# CIRCUIT.net
KiCad netlist of a schematic drawn in Altium Designer
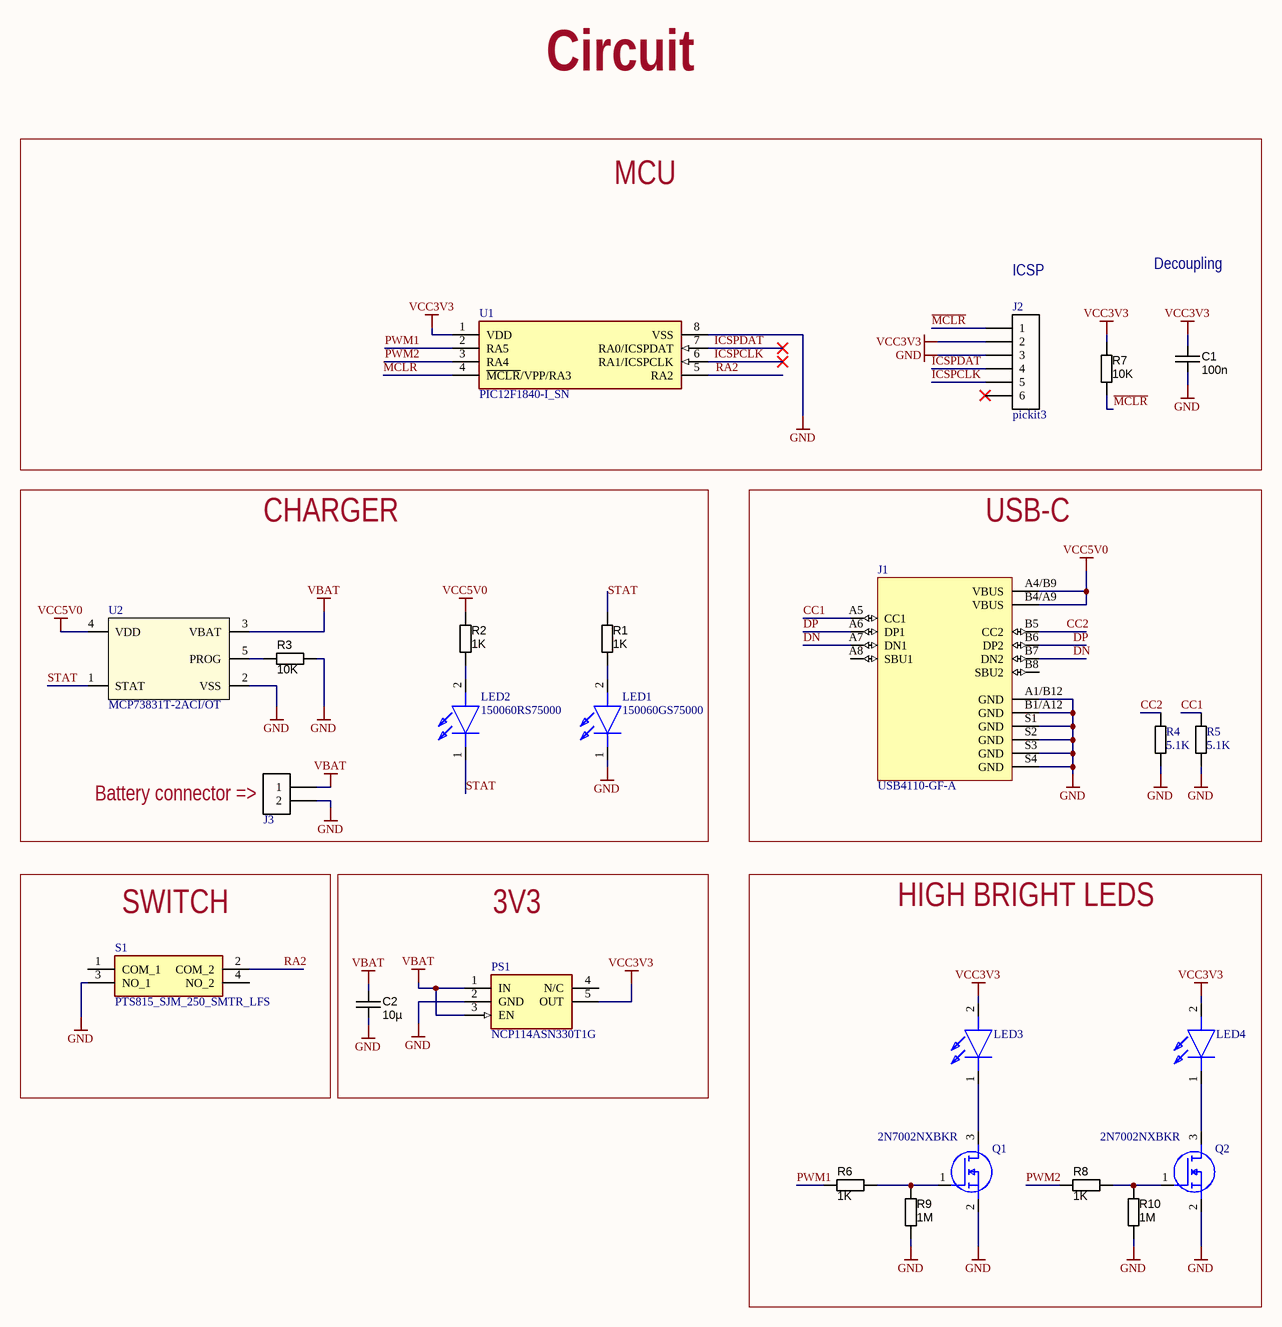
[diagram p0: CIRCUIT.SchDoc]

(export (version "E")
  (design (tool "Eeschema 10.0.6"))
  (components
    (comp (ref "C1")
      (value "100n")
      (footprint "CAPC1608X90N")
      (description "Capacitor SMD Cer 100nF 10% 50V X7R 0603")
      (fields (field (name "TOLERANCE") "±10%") (field (name "Comment") "approved sub OK"))
      (libsource (lib "PBL - Capacitors") (part "CAPC_100n_0603_X7R_50V_10%"))
    )
    (comp (ref "C2")
      (value "10µ")
      (footprint "CAPC3216X180N")
      (description "Capacitor SMD Cer 10uF 10% 25V X7R 1206")
      (fields (field (name "TOLERANCE") "±10%") (field (name "Comment") "approved sub OK"))
      (libsource (lib "jpnbino") (part "CAPC_10u_1206_25V"))
    )
    (comp (ref "J1")
      (value "USB4110-GF-A")
      (footprint "chico:GCT_USB4110-GF-A")
      (fields (field (name "MF") "GCT") (field (name "DIGI-KEY_PART_NUMBER") "2073-USB4110-GF-A-1-ND"))
      (libsource (lib "chico") (part "USB4110-GF-A"))
    )
    (comp (ref "J2")
      (value "pickit3")
      (footprint "CONN_ICSP")
      (description "CONN PROG PICKIT3 6VIAS")
      (libsource (lib "jpnbino") (part "CONN PROG PICKIT3"))
    )
    (comp (ref "J3")
      (value "S2B-PH-K-S(LF)(SN)")
      (footprint "JST-S2B-PH-K-S_V")
      (fields (field (name "TOLERANCE") "20%"))
      (libsource (lib "jpnbino") (part "CONN JST 2P 2MM"))
    )
    (comp (ref "LED1")
      (value "150060GS75000")
      (footprint "SamacSys:LEDC1608X80N")
      (description "LED")
      (fields (field (name "MOUSER PART NUMBER") "710-150060GS75000"))
      (libsource (lib "*") (part "150060GS75000"))
    )
    (comp (ref "LED2")
      (value "150060RS75000")
      (footprint "SamacSys:LEDC1608X80N")
      (description "LED")
      (fields (field (name "MOUSER PART NUMBER") "710-150060RS75000"))
      (libsource (lib "*") (part "150060RS75000"))
    )
    (comp (ref "LED3")
      (value "S1W0-2835408003-0000003S-00005")
      (footprint "SamacSys:STW8A12DMinJ18CAAll")
      (description "LED")
      (libsource (lib "SamacSys") (part "S1W0-2835408003-0000003S-00005"))
    )
    (comp (ref "LED4")
      (value "S1W0-2835408003-0000003S-00005")
      (footprint "SamacSys:STW8A12DMinJ18CAAll")
      (description "LED")
      (libsource (lib "SamacSys") (part "S1W0-2835408003-0000003S-00005"))
    )
    (comp (ref "PS1")
      (value "NCP114ASN330T1G")
      (footprint "SamacSys:SOT95P275X110-5N")
      (description "Power Supply")
      (fields (field (name "MOUSER PART NUMBER") "863-NCP114ASN330T1G"))
      (libsource (lib "*") (part "NCP114ASN330T1G"))
    )
    (comp (ref "Q1")
      (value "2N7002NXBKR")
      (footprint "SamacSys:SOT95P230X110-3N")
      (description "MOSFET (N-Channel)")
      (fields (field (name "MOUSER PART NUMBER") "771-2N7002NXBKR"))
      (libsource (lib "*") (part "2N7002NXBKR"))
    )
    (comp (ref "Q2")
      (value "2N7002NXBKR")
      (footprint "SamacSys:SOT95P230X110-3N")
      (description "MOSFET (N-Channel)")
      (fields (field (name "MOUSER PART NUMBER") "771-2N7002NXBKR"))
      (libsource (lib "*") (part "2N7002NXBKR"))
    )
    (comp (ref "R1")
      (value "1K")
      (footprint "RESC1608X55N")
      (description "Resistor SMD chip 1k Ohm 0.1W 5% 0603")
      (fields (field (name "TOLERANCE") "±5%") (field (name "Comment") "Thick Film"))
      (libsource (lib "PBL - Resistors") (part "RES_1K_0603_5%"))
    )
    (comp (ref "R2")
      (value "1K")
      (footprint "RESC1608X55N")
      (description "Resistor SMD chip 1k Ohm 0.1W 5% 0603")
      (fields (field (name "TOLERANCE") "±5%") (field (name "Comment") "Thick Film"))
      (libsource (lib "PBL - Resistors") (part "RES_1K_0603_5%"))
    )
    (comp (ref "R3")
      (value "10K")
      (footprint "RESC1608X55N")
      (description "Resistor SMD chip 10k Ohm 0.1W 5% 0603")
      (fields (field (name "TOLERANCE") "±5%") (field (name "Comment") "Thick Film"))
      (libsource (lib "") (part "RES_10K_0603_5%_1"))
    )
    (comp (ref "R4")
      (value "5.1K")
      (footprint "RESC1608X55N")
      (fields (field (name "Comment") "RES 5.1K OHM 5% 1/10W 0603"))
      (libsource (lib "jpnbino") (part "RES 5.1K OHM 5% 1/10W 0603"))
    )
    (comp (ref "R5")
      (value "5.1K")
      (footprint "RESC1608X55N")
      (fields (field (name "Comment") "RES 5.1K OHM 5% 1/10W 0603"))
      (libsource (lib "jpnbino") (part "RES 5.1K OHM 5% 1/10W 0603"))
    )
    (comp (ref "R6")
      (value "1K")
      (footprint "RESC1608X55N")
      (description "Resistor SMD chip 1k Ohm 0.1W 5% 0603")
      (fields (field (name "TOLERANCE") "±5%") (field (name "Comment") "Thick Film"))
      (libsource (lib "RRutledge") (part "RES_1K_0603_5%"))
    )
    (comp (ref "R7")
      (value "10K")
      (footprint "RESC1608X55N")
      (description "Resistor SMD chip 10k Ohm 0.1W 5% 0603")
      (fields (field (name "TOLERANCE") "±5%") (field (name "Comment") "Thick Film"))
      (libsource (lib "PBL - Resistors") (part "RES_10K_0603_5%"))
    )
    (comp (ref "R8")
      (value "1K")
      (footprint "RESC1608X55N")
      (description "Resistor SMD chip 1k Ohm 0.1W 5% 0603")
      (fields (field (name "TOLERANCE") "±5%") (field (name "Comment") "Thick Film"))
      (libsource (lib "RRutledge") (part "RES_1K_0603_5%"))
    )
    (comp (ref "R9")
      (value "1M")
      (footprint "RESC1608X55N")
      (description "Resistor SMD chip 1M Ohm 0.1W 5% 0603")
      (fields (field (name "TOLERANCE") "±5%") (field (name "Comment") "Thick Film"))
      (libsource (lib "RRutledge") (part "RES_1M_0603_5%"))
    )
    (comp (ref "R10")
      (value "1M")
      (footprint "RESC1608X55N")
      (description "Resistor SMD chip 1M Ohm 0.1W 5% 0603")
      (fields (field (name "TOLERANCE") "±5%") (field (name "Comment") "Thick Film"))
      (libsource (lib "RRutledge") (part "RES_1M_0603_5%"))
    )
    (comp (ref "S1")
      (value "PTS815_SJM_250_SMTR_LFS")
      (footprint "SamacSys:PTS815SJM250SMTRLFS")
      (description "Switch")
      (fields
        (field (name "MANUFACTURER_PART_NUMBER") "PTS815 SJM 250 SMTR LFS")
        (field (name "MOUSER PART NUMBER") "611-PTS815SJM250SMTR")
      )
      (libsource (lib "*") (part "PTS815_SJM_250_SMTR_LFS"))
    )
    (comp (ref "U1")
      (value "PIC12F1840-I_SN")
      (footprint "SamacSys:SOIC127P600X175-8N")
      (description "Integrated Circuit")
      (fields
        (field (name "MANUFACTURER_PART_NUMBER") "PIC12F1840-I/SN")
        (field (name "MOUSER PART NUMBER") "579-PIC12F1840-I/SN")
      )
      (libsource (lib "*") (part "PIC12F1840-I_SN"))
    )
    (comp (ref "U2")
      (value "MCP73831T-2ACI/OT")
      (footprint "chico:SOT-23-5_MC_MCH")
      (description "No Description Available")
      (fields (field (name "COPYRIGHT") "Copyright (C) 2018 Accelerated Designs. All rights reserved"))
      (libsource (lib "chico") (part "MCP73831T-2ACI/O"))
    )
  )
  (nets
    (net (code "1") (name "/CC1") (class "Default")
      (node (ref "J1") (pin "A5") (pinfunction "CC1_A5") (pintype "bidirectional"))
      (node (ref "R5") (pin "2") (pinfunction "2_2") (pintype "passive"))
    )
    (net (code "2") (name "/CC2") (class "Default")
      (node (ref "J1") (pin "B5") (pinfunction "CC2_B5") (pintype "bidirectional"))
      (node (ref "R4") (pin "2") (pinfunction "2_2") (pintype "passive"))
    )
    (net (code "3") (name "/DN") (class "Default")
      (node (ref "J1") (pin "A7") (pinfunction "DN1_A7") (pintype "bidirectional"))
      (node (ref "J1") (pin "B7") (pinfunction "DN2_B7") (pintype "bidirectional"))
    )
    (net (code "4") (name "/DP") (class "Default")
      (node (ref "J1") (pin "A6") (pinfunction "DP1_A6") (pintype "bidirectional"))
      (node (ref "J1") (pin "B6") (pinfunction "DP2_B6") (pintype "bidirectional"))
    )
    (net (code "5") (name "/ICSPCLK") (class "Default")
      (node (ref "J2") (pin "5") (pinfunction "5_5") (pintype "passive"))
      (node (ref "U1") (pin "6") (pinfunction "RA1/ICSPCLK_6") (pintype "input"))
    )
    (net (code "6") (name "/ICSPDAT") (class "Default")
      (node (ref "J2") (pin "4") (pinfunction "4_4") (pintype "passive"))
      (node (ref "U1") (pin "7") (pinfunction "RA0/ICSPDAT_7") (pintype "input"))
    )
    (net (code "7") (name "/PWM1") (class "Default")
      (node (ref "R6") (pin "1") (pinfunction "1_1") (pintype "passive"))
      (node (ref "U1") (pin "2") (pinfunction "RA5_2") (pintype "passive"))
    )
    (net (code "8") (name "/PWM2") (class "Default")
      (node (ref "R8") (pin "1") (pinfunction "1_1") (pintype "passive"))
      (node (ref "U1") (pin "3") (pinfunction "RA4_3") (pintype "passive"))
    )
    (net (code "9") (name "/RA2") (class "Default")
      (node (ref "S1") (pin "2") (pinfunction "COM_2_2") (pintype "passive"))
      (node (ref "U1") (pin "5") (pinfunction "RA2_5") (pintype "passive"))
    )
    (net (code "10") (name "/STAT") (class "Default")
      (node (ref "LED2") (pin "1") (pinfunction "K_1") (pintype "passive"))
      (node (ref "R1") (pin "1") (pinfunction "1_1") (pintype "passive"))
      (node (ref "U2") (pin "1") (pinfunction "STAT_1") (pintype "passive"))
    )
    (net (code "11") (name "/~{MCLR}") (class "Default")
      (node (ref "J2") (pin "1") (pinfunction "1_1") (pintype "passive"))
      (node (ref "R7") (pin "2") (pinfunction "2_2") (pintype "passive"))
      (node (ref "U1") (pin "4") (pinfunction "~{MCLR}/VPP/RA3_4") (pintype "passive"))
    )
    (net (code "12") (name "GND") (class "Default")
      (node (ref "C1") (pin "1") (pintype "passive"))
      (node (ref "C2") (pin "2") (pintype "passive"))
      (node (ref "J1") (pin "A1/B12") (pinfunction "GND_A1/B12") (pintype "power_in"))
      (node (ref "J1") (pin "B1/A12") (pinfunction "GND_B1/A12") (pintype "power_in"))
      (node (ref "J1") (pin "S1") (pinfunction "GND_S1") (pintype "power_in"))
      (node (ref "J1") (pin "S2") (pinfunction "GND_S2") (pintype "power_in"))
      (node (ref "J1") (pin "S3") (pinfunction "GND_S3") (pintype "power_in"))
      (node (ref "J1") (pin "S4") (pinfunction "GND_S4") (pintype "power_in"))
      (node (ref "J2") (pin "3") (pinfunction "3_3") (pintype "passive"))
      (node (ref "J3") (pin "2") (pinfunction "2_2") (pintype "passive"))
      (node (ref "LED1") (pin "1") (pinfunction "K_1") (pintype "passive"))
      (node (ref "PS1") (pin "2") (pinfunction "GND_2") (pintype "power_in"))
      (node (ref "Q1") (pin "2") (pinfunction "S_2") (pintype "passive"))
      (node (ref "Q2") (pin "2") (pinfunction "S_2") (pintype "passive"))
      (node (ref "R10") (pin "2") (pinfunction "2_2") (pintype "passive"))
      (node (ref "R3") (pin "2") (pinfunction "2_2") (pintype "passive"))
      (node (ref "R4") (pin "1") (pinfunction "1_1") (pintype "passive"))
      (node (ref "R5") (pin "1") (pinfunction "1_1") (pintype "passive"))
      (node (ref "R9") (pin "2") (pinfunction "2_2") (pintype "passive"))
      (node (ref "S1") (pin "3") (pinfunction "NO_1_3") (pintype "passive"))
      (node (ref "U1") (pin "8") (pinfunction "VSS_8") (pintype "power_in"))
      (node (ref "U2") (pin "2") (pinfunction "VSS_2") (pintype "passive"))
    )
    (net (code "13") (name "Net-(LED1-A)") (class "Default")
      (node (ref "LED1") (pin "2") (pinfunction "A_2") (pintype "passive"))
      (node (ref "R1") (pin "2") (pinfunction "2_2") (pintype "passive"))
    )
    (net (code "14") (name "Net-(LED2-A)") (class "Default")
      (node (ref "LED2") (pin "2") (pinfunction "A_2") (pintype "passive"))
      (node (ref "R2") (pin "2") (pinfunction "2_2") (pintype "passive"))
    )
    (net (code "15") (name "Net-(LED3-K)") (class "Default")
      (node (ref "LED3") (pin "1") (pinfunction "K_1") (pintype "passive"))
      (node (ref "Q1") (pin "3") (pinfunction "D_3") (pintype "passive"))
    )
    (net (code "16") (name "Net-(LED4-K)") (class "Default")
      (node (ref "LED4") (pin "1") (pinfunction "K_1") (pintype "passive"))
      (node (ref "Q2") (pin "3") (pinfunction "D_3") (pintype "passive"))
    )
    (net (code "17") (name "Net-(Q1-G)") (class "Default")
      (node (ref "Q1") (pin "1") (pinfunction "G_1") (pintype "passive"))
      (node (ref "R6") (pin "2") (pinfunction "2_2") (pintype "passive"))
      (node (ref "R9") (pin "1") (pinfunction "1_1") (pintype "passive"))
    )
    (net (code "18") (name "Net-(Q2-G)") (class "Default")
      (node (ref "Q2") (pin "1") (pinfunction "G_1") (pintype "passive"))
      (node (ref "R10") (pin "1") (pinfunction "1_1") (pintype "passive"))
      (node (ref "R8") (pin "2") (pinfunction "2_2") (pintype "passive"))
    )
    (net (code "19") (name "Net-(U2-PROG)") (class "Default")
      (node (ref "R3") (pin "1") (pinfunction "1_1") (pintype "passive"))
      (node (ref "U2") (pin "5") (pinfunction "PROG_5") (pintype "passive"))
    )
    (net (code "20") (name "VBAT") (class "Default")
      (node (ref "C2") (pin "1") (pintype "passive"))
      (node (ref "J3") (pin "1") (pinfunction "1_1") (pintype "passive"))
      (node (ref "PS1") (pin "1") (pinfunction "IN_1") (pintype "power_in"))
      (node (ref "PS1") (pin "3") (pinfunction "EN_3") (pintype "input"))
      (node (ref "U2") (pin "3") (pinfunction "VBAT_3") (pintype "passive"))
    )
    (net (code "21") (name "VCC3V3") (class "Default")
      (node (ref "C1") (pin "2") (pintype "passive"))
      (node (ref "J2") (pin "2") (pinfunction "2_2") (pintype "passive"))
      (node (ref "LED3") (pin "2") (pinfunction "A_2") (pintype "passive"))
      (node (ref "LED4") (pin "2") (pinfunction "A_2") (pintype "passive"))
      (node (ref "PS1") (pin "5") (pinfunction "OUT_5") (pintype "power_in"))
      (node (ref "R7") (pin "1") (pinfunction "1_1") (pintype "passive"))
      (node (ref "U1") (pin "1") (pinfunction "VDD_1") (pintype "power_in"))
    )
    (net (code "22") (name "VCC5V0") (class "Default")
      (node (ref "J1") (pin "A4/B9") (pinfunction "VBUS_A4/B9") (pintype "power_in"))
      (node (ref "J1") (pin "B4/A9") (pinfunction "VBUS_B4/A9") (pintype "power_in"))
      (node (ref "R2") (pin "1") (pinfunction "1_1") (pintype "passive"))
      (node (ref "U2") (pin "4") (pinfunction "VDD_4") (pintype "passive"))
    )
    (net (code "23") (name "unconnected-(J1-SBU1-PadA8)") (class "Default")
      (node (ref "J1") (pin "A8") (pinfunction "SBU1_A8") (pintype "bidirectional"))
    )
    (net (code "24") (name "unconnected-(J1-SBU2-PadB8)") (class "Default")
      (node (ref "J1") (pin "B8") (pinfunction "SBU2_B8") (pintype "bidirectional"))
    )
    (net (code "25") (name "unconnected-(J2-Pad6)") (class "Default")
      (node (ref "J2") (pin "6") (pinfunction "6_6") (pintype "passive+no_connect"))
    )
    (net (code "26") (name "unconnected-(PS1-N{slash}C-Pad4)") (class "Default")
      (node (ref "PS1") (pin "4") (pinfunction "N/C_4") (pintype "passive"))
    )
    (net (code "27") (name "unconnected-(S1-COM_1-Pad1)") (class "Default")
      (node (ref "S1") (pin "1") (pinfunction "COM_1_1") (pintype "passive"))
    )
    (net (code "28") (name "unconnected-(S1-NO_2-Pad4)") (class "Default")
      (node (ref "S1") (pin "4") (pinfunction "NO_2_4") (pintype "passive"))
    )
  )
)
